# RT1064_Device.net
KiCad netlist of a schematic drawn in Altium Designer
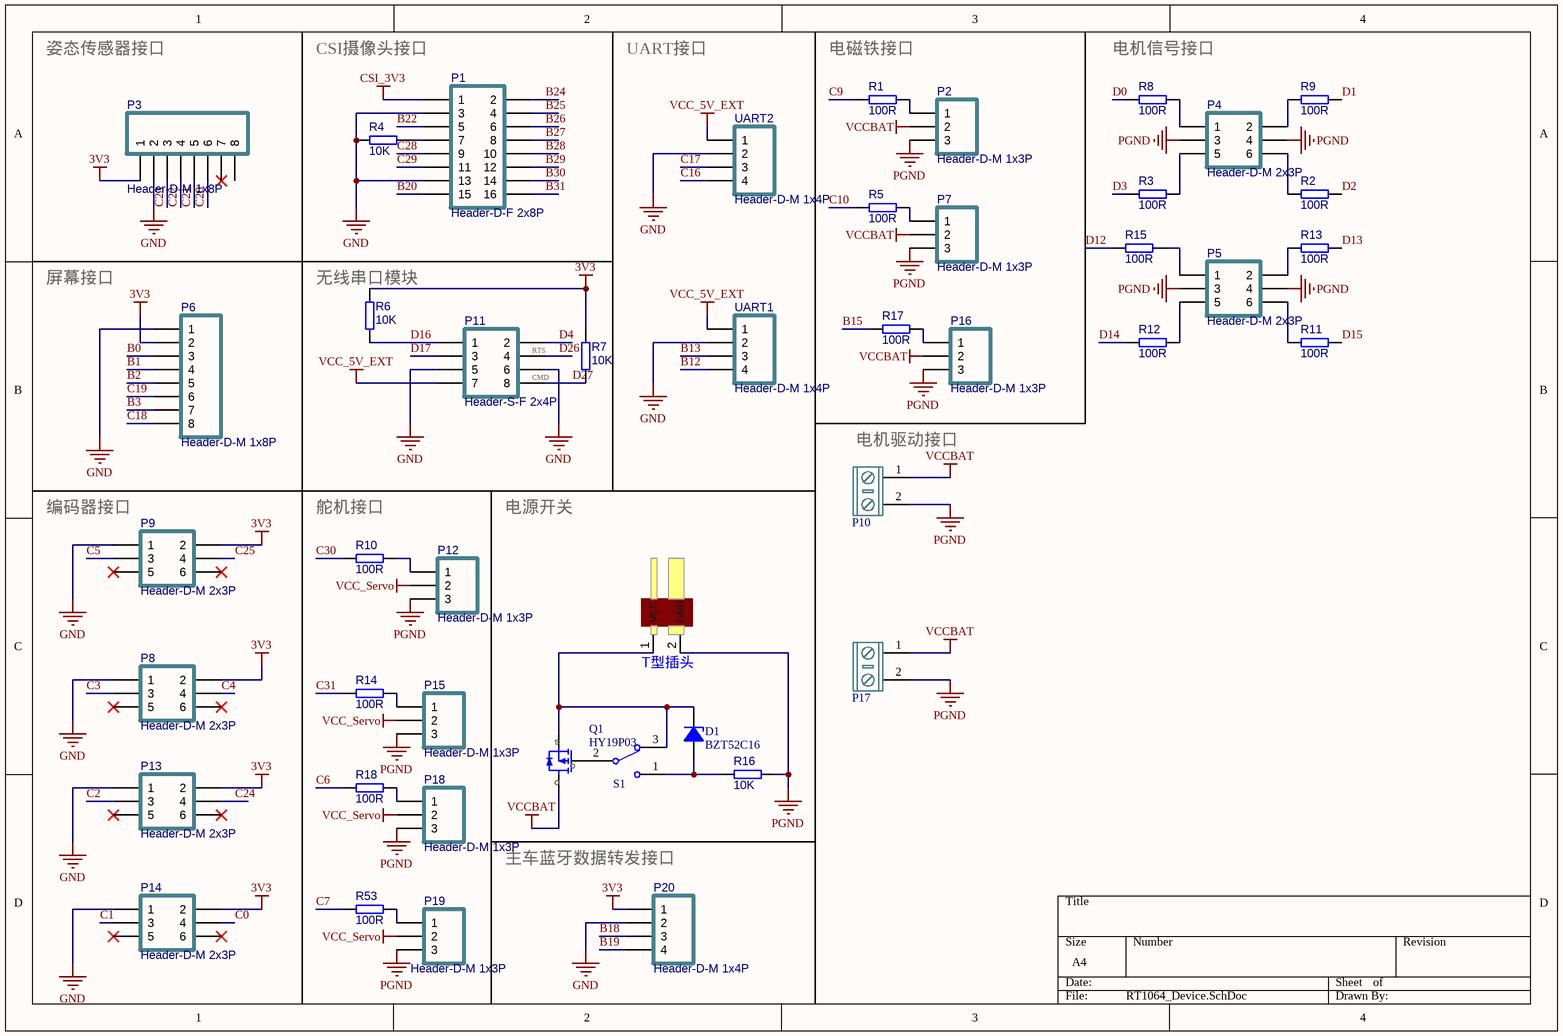
[diagram p0: RT1064_Device.SchDoc]

(export (version "E")
  (design (tool "Eeschema 10.0.6"))
  (components
    (comp (ref "D1")
      (value "BZT52C16")
      (footprint "SOD-123-L")
      (description "稳压二极管 齐纳二极管  Zener Diode")
      (fields (field (name "PUBLISHER") "Altium Limited"))
      (libsource (lib "RT1064_V1主板器件封装集成库") (part "Diode Zen"))
    )
    (comp (ref "DCIN1")
      (value "T型插头")
      (footprint "CONN-TH_AM-1015B-F")
      (libsource (lib "RT1064_V1主板器件封装集成库") (part "T_Header"))
    )
    (comp (ref "P1")
      (value "Header-D-F 2x8P")
      (footprint "Cam_HDR2X8-F-SMT")
      (description "2x8pin, 直插, 双排座")
      (libsource (lib "RT1064 主板 V3.0 器件封装集成库") (part "Header-D-F 2x8P"))
    )
    (comp (ref "P2")
      (value "Header-D-M 1x3P")
      (footprint "HDR1X3-M")
      (description "1x3pin, 直插, 排针")
      (libsource (lib "RT1064_V1主板器件封装集成库") (part "Header-D-M 1x3P"))
    )
    (comp (ref "P3")
      (value "Header-D-M 1x8P")
      (footprint "Fe-HDR1X8/2.54-S")
      (description "1x8pin, 直插, 排针")
      (libsource (lib "RT1064_V1主板器件封装集成库") (part "Header-D-M 1x8P"))
    )
    (comp (ref "P4")
      (value "Header-D-M 2x3P")
      (footprint "HDR2.54-M-LS-2x3P")
      (description "2x3pin, 贴片, 双排针")
      (libsource (lib "RT1064_V1主板器件封装集成库") (part "Header-S-M 2x3P"))
    )
    (comp (ref "P5")
      (value "Header-D-M 2x3P")
      (footprint "HDR2.54-M-LS-2x3P")
      (description "2x3pin, 贴片, 双排针")
      (libsource (lib "RT1064_V1主板器件封装集成库") (part "Header-S-M 2x3P"))
    )
    (comp (ref "P6")
      (value "Header-D-M 1x8P")
      (footprint "Fe-HDR1X8/2.54-S")
      (description "1x8pin, 直插, 排针")
      (libsource (lib "") (part "Header-D-M 1x8P_1"))
    )
    (comp (ref "P7")
      (value "Header-D-M 1x3P")
      (footprint "HDR1X3-M")
      (description "1x3pin, 直插, 排针")
      (libsource (lib "RT1064_V1主板器件封装集成库") (part "Header-D-M 1x3P"))
    )
    (comp (ref "P8")
      (value "Header-D-M 2x3P")
      (footprint "DC3-6P-2.54mm")
      (description "2x3pin, 贴片, 双排针")
      (libsource (lib "RT1064_V1主板器件封装集成库") (part "Header-S-M 2x3P"))
    )
    (comp (ref "P9")
      (value "Header-D-M 2x3P")
      (footprint "DC3-6P-2.54mm")
      (description "2x3pin, 贴片, 双排针")
      (libsource (lib "RT1064_V1主板器件封装集成库") (part "Header-S-M 2x3P"))
    )
    (comp (ref "P10")
      (value "KF/WJ/DG 30x connecter")
      (footprint "KF/WJ/DG 301-2p-5.0mm")
      (description "接线端子 2Pin")
      (libsource (lib "RT1064_V1主板器件封装集成库") (part "KF/WJ/DG 30x"))
    )
    (comp (ref "P11")
      (value "Header-S-F 2x4P")
      (footprint "HDR2X4-F-SMT")
      (description "2x4pin, 贴片, 双排座")
      (libsource (lib "RT1064_V1主板器件封装集成库") (part "Header-S-F 2x4P"))
    )
    (comp (ref "P12")
      (value "Header-D-M 1x3P")
      (footprint "Fe-HDR1X3/2.54-S")
      (description "1x3pin, 直插, 排针")
      (libsource (lib "RT1064_V1主板器件封装集成库") (part "Header-D-M 1x3P"))
    )
    (comp (ref "P13")
      (value "Header-D-M 2x3P")
      (footprint "DC3-6P-2.54mm")
      (description "2x3pin, 贴片, 双排针")
      (libsource (lib "RT1064_V1主板器件封装集成库") (part "Header-S-M 2x3P"))
    )
    (comp (ref "P14")
      (value "Header-D-M 2x3P")
      (footprint "DC3-6P-2.54mm")
      (description "2x3pin, 贴片, 双排针")
      (libsource (lib "RT1064_V1主板器件封装集成库") (part "Header-S-M 2x3P"))
    )
    (comp (ref "P15")
      (value "Header-D-M 1x3P")
      (footprint "Fe-HDR1X3/2.54-S")
      (description "1x3pin, 直插, 排针")
      (libsource (lib "RT1064_V1主板器件封装集成库") (part "Header-D-M 1x3P"))
    )
    (comp (ref "P16")
      (value "Header-D-M 1x3P")
      (footprint "HDR1X3-M")
      (description "1x3pin, 直插, 排针")
      (libsource (lib "RT1064_V1主板器件封装集成库") (part "Header-D-M 1x3P"))
    )
    (comp (ref "P17")
      (value "KF/WJ/DG 30x connecter")
      (footprint "KF/WJ/DG 301-2p-5.0mm")
      (description "接线端子 2Pin")
      (libsource (lib "RT1064_V1主板器件封装集成库") (part "KF/WJ/DG 30x"))
    )
    (comp (ref "P18")
      (value "Header-D-M 1x3P")
      (footprint "Fe-HDR1X3/2.54-S")
      (description "1x3pin, 直插, 排针")
      (libsource (lib "RT1064_V1主板器件封装集成库") (part "Header-D-M 1x3P"))
    )
    (comp (ref "P19")
      (value "Header-D-M 1x3P")
      (footprint "Fe-HDR1X3/2.54-S")
      (description "1x3pin, 直插, 排针")
      (libsource (lib "RT1064_V1主板器件封装集成库") (part "Header-D-M 1x3P"))
    )
    (comp (ref "P20")
      (value "Header-D-M 1x4P")
      (footprint "HDR1X4-M")
      (description "1x4pin, 直插, 排针")
      (libsource (lib "RT1064_V1主板器件封装集成库") (part "Header-D-M 1x4P"))
    )
    (comp (ref "Q1")
      (value "HY19P03")
      (footprint "TO-252AA")
      (description "HY19P03 P-Channel MOSFET")
      (libsource (lib "RT1064_V1主板器件封装集成库") (part "HY19P03"))
    )
    (comp (ref "R1")
      (value "100R")
      (footprint "RESC1608[0603]S-L")
      (description "贴片电阻")
      (fields (field (name "POWER") "1/8W") (field (name "TOLERANCE") "±1%"))
      (libsource (lib "RT1064_V1主板器件封装集成库") (part "Res-Chip"))
    )
    (comp (ref "R2")
      (value "100R")
      (footprint "RESC1608[0603]S-L")
      (description "贴片电阻")
      (fields (field (name "POWER") "1/8W") (field (name "TOLERANCE") "±1%"))
      (libsource (lib "RT1064_V1主板器件封装集成库") (part "Res-Chip"))
    )
    (comp (ref "R3")
      (value "100R")
      (footprint "RESC1608[0603]S-L")
      (description "贴片电阻")
      (fields (field (name "POWER") "1/8W") (field (name "TOLERANCE") "±1%"))
      (libsource (lib "RT1064_V1主板器件封装集成库") (part "Res-Chip"))
    )
    (comp (ref "R4")
      (value "10K")
      (footprint "RESC1608[0603]S-L")
      (description "贴片电阻")
      (fields (field (name "POWER") "1/8W") (field (name "TOLERANCE") "±1%"))
      (libsource (lib "RT1064_V1主板器件封装集成库") (part "Res-Chip"))
    )
    (comp (ref "R5")
      (value "100R")
      (footprint "RESC1608[0603]S-L")
      (description "贴片电阻")
      (fields (field (name "POWER") "1/8W") (field (name "TOLERANCE") "±1%"))
      (libsource (lib "RT1064_V1主板器件封装集成库") (part "Res-Chip"))
    )
    (comp (ref "R6")
      (value "10K")
      (footprint "RESC1608[0603]S-L")
      (description "贴片电阻")
      (fields (field (name "POWER") "1/8W") (field (name "TOLERANCE") "±1%"))
      (libsource (lib "RT1064_V1主板器件封装集成库") (part "Res-Chip"))
    )
    (comp (ref "R7")
      (value "10K")
      (footprint "RESC1608[0603]S-L")
      (description "贴片电阻")
      (fields (field (name "POWER") "1/8W") (field (name "TOLERANCE") "±1%"))
      (libsource (lib "RT1064_V1主板器件封装集成库") (part "Res-Chip"))
    )
    (comp (ref "R8")
      (value "100R")
      (footprint "RESC1608[0603]S-L")
      (description "贴片电阻")
      (fields (field (name "POWER") "1/8W") (field (name "TOLERANCE") "±1%"))
      (libsource (lib "RT1064_V1主板器件封装集成库") (part "Res-Chip"))
    )
    (comp (ref "R9")
      (value "100R")
      (footprint "RESC1608[0603]S-L")
      (description "贴片电阻")
      (fields (field (name "POWER") "1/8W") (field (name "TOLERANCE") "±1%"))
      (libsource (lib "RT1064_V1主板器件封装集成库") (part "Res-Chip"))
    )
    (comp (ref "R10")
      (value "100R")
      (footprint "RESC1608[0603]S-L")
      (description "贴片电阻")
      (fields (field (name "POWER") "1/8W") (field (name "TOLERANCE") "±1%"))
      (libsource (lib "RT1064_V1主板器件封装集成库") (part "Res-Chip"))
    )
    (comp (ref "R11")
      (value "100R")
      (footprint "RESC1608[0603]S-L")
      (description "贴片电阻")
      (fields (field (name "POWER") "1/8W") (field (name "TOLERANCE") "±1%"))
      (libsource (lib "RT1064_V1主板器件封装集成库") (part "Res-Chip"))
    )
    (comp (ref "R12")
      (value "100R")
      (footprint "RESC1608[0603]S-L")
      (description "贴片电阻")
      (fields (field (name "POWER") "1/8W") (field (name "TOLERANCE") "±1%"))
      (libsource (lib "RT1064_V1主板器件封装集成库") (part "Res-Chip"))
    )
    (comp (ref "R13")
      (value "100R")
      (footprint "RESC1608[0603]S-L")
      (description "贴片电阻")
      (fields (field (name "POWER") "1/8W") (field (name "TOLERANCE") "±1%"))
      (libsource (lib "RT1064_V1主板器件封装集成库") (part "Res-Chip"))
    )
    (comp (ref "R14")
      (value "100R")
      (footprint "RESC1608[0603]S-L")
      (description "贴片电阻")
      (fields (field (name "POWER") "1/8W") (field (name "TOLERANCE") "±1%"))
      (libsource (lib "RT1064_V1主板器件封装集成库") (part "Res-Chip"))
    )
    (comp (ref "R15")
      (value "100R")
      (footprint "RESC1608[0603]S-L")
      (description "贴片电阻")
      (fields (field (name "POWER") "1/8W") (field (name "TOLERANCE") "±1%"))
      (libsource (lib "RT1064_V1主板器件封装集成库") (part "Res-Chip"))
    )
    (comp (ref "R16")
      (value "10K")
      (footprint "RESC1608[0603]S-L")
      (description "贴片电阻")
      (fields (field (name "POWER") "1/8W") (field (name "TOLERANCE") "±1%"))
      (libsource (lib "RT1064_V1主板器件封装集成库") (part "Res-Chip"))
    )
    (comp (ref "R17")
      (value "100R")
      (footprint "RESC1608[0603]S-L")
      (description "贴片电阻")
      (fields (field (name "POWER") "1/8W") (field (name "TOLERANCE") "±1%"))
      (libsource (lib "RT1064_V1主板器件封装集成库") (part "Res-Chip"))
    )
    (comp (ref "R18")
      (value "100R")
      (footprint "RESC1608[0603]S-L")
      (description "贴片电阻")
      (fields (field (name "POWER") "1/8W") (field (name "TOLERANCE") "±1%"))
      (libsource (lib "RT1064_V1主板器件封装集成库") (part "Res-Chip"))
    )
    (comp (ref "R53")
      (value "100R")
      (footprint "RESC1608[0603]S-L")
      (description "贴片电阻")
      (fields (field (name "POWER") "1/8W") (field (name "TOLERANCE") "±1%"))
      (libsource (lib "RT1064_V1主板器件封装集成库") (part "Res-Chip"))
    )
    (comp (ref "S1")
      (value "SW-SPDT")
      (footprint "SS-12F23")
      (description "单刀双掷开关 3脚船型、钮子、拨动开关 SPDT Subminiature Toggle Switch")
      (fields (field (name "PUBLISHER") "Altium Limited"))
      (libsource (lib "RT1064_V1主板器件封装集成库") (part "SW-SPDT"))
    )
    (comp (ref "UART1")
      (value "Header-D-M 1x4P")
      (footprint "XH2.54-WI-4P")
      (description "1x4pin, 直插, 排针")
      (libsource (lib "RT1064_V1主板器件封装集成库") (part "Header-D-M 1x4P"))
    )
    (comp (ref "UART2")
      (value "Header-D-M 1x4P")
      (footprint "XH2.54-WI-4P")
      (description "1x4pin, 直插, 排针")
      (libsource (lib "RT1064_V1主板器件封装集成库") (part "Header-D-M 1x4P"))
    )
  )
  (nets
    (net (code "1") (name "/B0") (class "Default")
      (node (ref "P6") (pin "3") (pinfunction "3_3") (pintype "passive"))
    )
    (net (code "2") (name "/B1") (class "Default")
      (node (ref "P6") (pin "4") (pinfunction "4_4") (pintype "passive"))
    )
    (net (code "3") (name "/B2") (class "Default")
      (node (ref "P6") (pin "5") (pinfunction "5_5") (pintype "passive"))
    )
    (net (code "4") (name "/B3") (class "Default")
      (node (ref "P6") (pin "7") (pinfunction "7_7") (pintype "passive"))
    )
    (net (code "5") (name "/B12") (class "Default")
      (node (ref "UART1") (pin "4") (pinfunction "4_4") (pintype "passive"))
    )
    (net (code "6") (name "/B13") (class "Default")
      (node (ref "UART1") (pin "3") (pinfunction "3_3") (pintype "passive"))
    )
    (net (code "7") (name "/B15") (class "Default")
      (node (ref "R17") (pin "2") (pinfunction "2_2") (pintype "passive"))
    )
    (net (code "8") (name "/B18") (class "Default")
      (node (ref "P20") (pin "3") (pinfunction "3_3") (pintype "passive"))
    )
    (net (code "9") (name "/B19") (class "Default")
      (node (ref "P20") (pin "4") (pinfunction "4_4") (pintype "passive"))
    )
    (net (code "10") (name "/B20") (class "Default")
      (node (ref "P1") (pin "15") (pinfunction "15_15") (pintype "passive"))
    )
    (net (code "11") (name "/B22") (class "Default")
      (node (ref "P1") (pin "5") (pinfunction "5_5") (pintype "passive"))
    )
    (net (code "12") (name "/B24") (class "Default")
      (node (ref "P1") (pin "2") (pinfunction "2_2") (pintype "passive"))
    )
    (net (code "13") (name "/B25") (class "Default")
      (node (ref "P1") (pin "4") (pinfunction "4_4") (pintype "passive"))
    )
    (net (code "14") (name "/B26") (class "Default")
      (node (ref "P1") (pin "6") (pinfunction "6_6") (pintype "passive"))
    )
    (net (code "15") (name "/B27") (class "Default")
      (node (ref "P1") (pin "8") (pinfunction "8_8") (pintype "passive"))
    )
    (net (code "16") (name "/B28") (class "Default")
      (node (ref "P1") (pin "10") (pinfunction "10_10") (pintype "passive"))
    )
    (net (code "17") (name "/B29") (class "Default")
      (node (ref "P1") (pin "12") (pinfunction "12_12") (pintype "passive"))
    )
    (net (code "18") (name "/B30") (class "Default")
      (node (ref "P1") (pin "14") (pinfunction "14_14") (pintype "passive"))
    )
    (net (code "19") (name "/B31") (class "Default")
      (node (ref "P1") (pin "16") (pinfunction "16_16") (pintype "passive"))
    )
    (net (code "20") (name "/C0") (class "Default")
      (node (ref "P14") (pin "4") (pinfunction "4_4") (pintype "passive"))
    )
    (net (code "21") (name "/C1") (class "Default")
      (node (ref "P14") (pin "3") (pinfunction "3_3") (pintype "passive"))
    )
    (net (code "22") (name "/C2") (class "Default")
      (node (ref "P13") (pin "3") (pinfunction "3_3") (pintype "passive"))
    )
    (net (code "23") (name "/C3") (class "Default")
      (node (ref "P8") (pin "3") (pinfunction "3_3") (pintype "passive"))
    )
    (net (code "24") (name "/C4") (class "Default")
      (node (ref "P8") (pin "4") (pinfunction "4_4") (pintype "passive"))
    )
    (net (code "25") (name "/C5") (class "Default")
      (node (ref "P9") (pin "3") (pinfunction "3_3") (pintype "passive"))
    )
    (net (code "26") (name "/C6") (class "Default")
      (node (ref "R18") (pin "2") (pinfunction "2_2") (pintype "passive"))
    )
    (net (code "27") (name "/C7") (class "Default")
      (node (ref "R53") (pin "2") (pinfunction "2_2") (pintype "passive"))
    )
    (net (code "28") (name "/C9") (class "Default")
      (node (ref "R1") (pin "2") (pinfunction "2_2") (pintype "passive"))
    )
    (net (code "29") (name "/C10") (class "Default")
      (node (ref "R5") (pin "2") (pinfunction "2_2") (pintype "passive"))
    )
    (net (code "30") (name "/C16") (class "Default")
      (node (ref "UART2") (pin "4") (pinfunction "4_4") (pintype "passive"))
    )
    (net (code "31") (name "/C17") (class "Default")
      (node (ref "UART2") (pin "3") (pinfunction "3_3") (pintype "passive"))
    )
    (net (code "32") (name "/C18") (class "Default")
      (node (ref "P6") (pin "8") (pinfunction "8_8") (pintype "passive"))
    )
    (net (code "33") (name "/C19") (class "Default")
      (node (ref "P6") (pin "6") (pinfunction "6_6") (pintype "passive"))
    )
    (net (code "34") (name "/C20") (class "Default")
      (node (ref "P3") (pin "6") (pinfunction "6_6") (pintype "passive"))
    )
    (net (code "35") (name "/C21") (class "Default")
      (node (ref "P3") (pin "5") (pinfunction "5_5") (pintype "passive"))
    )
    (net (code "36") (name "/C22") (class "Default")
      (node (ref "P3") (pin "4") (pinfunction "4_4") (pintype "passive"))
    )
    (net (code "37") (name "/C23") (class "Default")
      (node (ref "P3") (pin "3") (pinfunction "3_3") (pintype "passive"))
    )
    (net (code "38") (name "/C24") (class "Default")
      (node (ref "P13") (pin "4") (pinfunction "4_4") (pintype "passive"))
    )
    (net (code "39") (name "/C25") (class "Default")
      (node (ref "P9") (pin "4") (pinfunction "4_4") (pintype "passive"))
    )
    (net (code "40") (name "/C28") (class "Default")
      (node (ref "P1") (pin "9") (pinfunction "9_9") (pintype "passive"))
    )
    (net (code "41") (name "/C29") (class "Default")
      (node (ref "P1") (pin "11") (pinfunction "11_11") (pintype "passive"))
    )
    (net (code "42") (name "/C30") (class "Default")
      (node (ref "R10") (pin "2") (pinfunction "2_2") (pintype "passive"))
    )
    (net (code "43") (name "/C31") (class "Default")
      (node (ref "R14") (pin "2") (pinfunction "2_2") (pintype "passive"))
    )
    (net (code "44") (name "/D0") (class "Default")
      (node (ref "R8") (pin "1") (pinfunction "1_1") (pintype "passive"))
    )
    (net (code "45") (name "/D1") (class "Default")
      (node (ref "R9") (pin "1") (pinfunction "1_1") (pintype "passive"))
    )
    (net (code "46") (name "/D2") (class "Default")
      (node (ref "R2") (pin "1") (pinfunction "1_1") (pintype "passive"))
    )
    (net (code "47") (name "/D3") (class "Default")
      (node (ref "R3") (pin "1") (pinfunction "1_1") (pintype "passive"))
    )
    (net (code "48") (name "/D4") (class "Default")
      (node (ref "P11") (pin "2") (pinfunction "2_2") (pintype "passive"))
    )
    (net (code "49") (name "/D12") (class "Default")
      (node (ref "R15") (pin "1") (pinfunction "1_1") (pintype "passive"))
    )
    (net (code "50") (name "/D13") (class "Default")
      (node (ref "R13") (pin "1") (pinfunction "1_1") (pintype "passive"))
    )
    (net (code "51") (name "/D14") (class "Default")
      (node (ref "R12") (pin "1") (pinfunction "1_1") (pintype "passive"))
    )
    (net (code "52") (name "/D15") (class "Default")
      (node (ref "R11") (pin "1") (pinfunction "1_1") (pintype "passive"))
    )
    (net (code "53") (name "/D16") (class "Default")
      (node (ref "P11") (pin "1") (pinfunction "1_1") (pintype "passive"))
      (node (ref "R6") (pin "1") (pinfunction "1_1") (pintype "passive"))
    )
    (net (code "54") (name "/D17") (class "Default")
      (node (ref "P11") (pin "3") (pinfunction "3_3") (pintype "passive"))
    )
    (net (code "55") (name "/D26") (class "Default")
      (node (ref "P11") (pin "4") (pinfunction "4_4") (pintype "passive"))
    )
    (net (code "56") (name "/D27") (class "Default")
      (node (ref "P11") (pin "8") (pinfunction "8_8") (pintype "passive"))
      (node (ref "R7") (pin "1") (pinfunction "1_1") (pintype "passive"))
    )
    (net (code "57") (name "3V3") (class "Default")
      (node (ref "P13") (pin "2") (pinfunction "2_2") (pintype "passive"))
      (node (ref "P14") (pin "2") (pinfunction "2_2") (pintype "passive"))
      (node (ref "P20") (pin "1") (pinfunction "1_1") (pintype "passive"))
      (node (ref "P3") (pin "1") (pinfunction "1_1") (pintype "passive"))
      (node (ref "P6") (pin "2") (pinfunction "2_2") (pintype "passive"))
      (node (ref "P8") (pin "2") (pinfunction "2_2") (pintype "passive"))
      (node (ref "P9") (pin "2") (pinfunction "2_2") (pintype "passive"))
      (node (ref "R6") (pin "2") (pinfunction "2_2") (pintype "passive"))
      (node (ref "R7") (pin "2") (pinfunction "2_2") (pintype "passive"))
    )
    (net (code "58") (name "CSI_3V3") (class "Default")
      (node (ref "P1") (pin "1") (pinfunction "1_1") (pintype "passive"))
    )
    (net (code "59") (name "GND") (class "Default")
      (node (ref "P1") (pin "13") (pinfunction "13_13") (pintype "passive"))
      (node (ref "P1") (pin "3") (pinfunction "3_3") (pintype "passive"))
      (node (ref "P11") (pin "5") (pinfunction "5_5") (pintype "passive"))
      (node (ref "P11") (pin "6") (pinfunction "6_6") (pintype "passive"))
      (node (ref "P13") (pin "1") (pinfunction "1_1") (pintype "passive"))
      (node (ref "P14") (pin "1") (pinfunction "1_1") (pintype "passive"))
      (node (ref "P20") (pin "2") (pinfunction "2_2") (pintype "passive"))
      (node (ref "P3") (pin "2") (pinfunction "2_2") (pintype "passive"))
      (node (ref "P6") (pin "1") (pinfunction "1_1") (pintype "passive"))
      (node (ref "P8") (pin "1") (pinfunction "1_1") (pintype "passive"))
      (node (ref "P9") (pin "1") (pinfunction "1_1") (pintype "passive"))
      (node (ref "R4") (pin "2") (pinfunction "2_2") (pintype "passive"))
      (node (ref "UART1") (pin "2") (pinfunction "2_2") (pintype "passive"))
      (node (ref "UART2") (pin "2") (pinfunction "2_2") (pintype "passive"))
    )
    (net (code "60") (name "Net-(D1-PadA)") (class "Default")
      (node (ref "D1") (pin "A") (pinfunction "A_A") (pintype "passive"))
      (node (ref "R16") (pin "2") (pinfunction "2_2") (pintype "passive"))
      (node (ref "S1") (pin "1") (pintype "passive"))
    )
    (net (code "61") (name "Net-(DCIN1-VCC)") (class "Default")
      (node (ref "D1") (pin "K") (pinfunction "K_K") (pintype "passive"))
      (node (ref "DCIN1") (pin "1") (pinfunction "VCC_1") (pintype "passive"))
      (node (ref "Q1") (pin "3") (pinfunction "S_3") (pintype "passive"))
      (node (ref "S1") (pin "3") (pintype "passive"))
    )
    (net (code "62") (name "Net-(P1-Pad7)") (class "Default")
      (node (ref "P1") (pin "7") (pinfunction "7_7") (pintype "passive"))
      (node (ref "R4") (pin "1") (pinfunction "1_1") (pintype "passive"))
    )
    (net (code "63") (name "Net-(P2-Pad1)") (class "Default")
      (node (ref "P2") (pin "1") (pinfunction "1_1") (pintype "passive"))
      (node (ref "R1") (pin "1") (pinfunction "1_1") (pintype "passive"))
    )
    (net (code "64") (name "Net-(P4-Pad1)") (class "Default")
      (node (ref "P4") (pin "1") (pinfunction "1_1") (pintype "passive"))
      (node (ref "R8") (pin "2") (pinfunction "2_2") (pintype "passive"))
    )
    (net (code "65") (name "Net-(P4-Pad2)") (class "Default")
      (node (ref "P4") (pin "2") (pinfunction "2_2") (pintype "passive"))
      (node (ref "R9") (pin "2") (pinfunction "2_2") (pintype "passive"))
    )
    (net (code "66") (name "Net-(P4-Pad5)") (class "Default")
      (node (ref "P4") (pin "5") (pinfunction "5_5") (pintype "passive"))
      (node (ref "R3") (pin "2") (pinfunction "2_2") (pintype "passive"))
    )
    (net (code "67") (name "Net-(P4-Pad6)") (class "Default")
      (node (ref "P4") (pin "6") (pinfunction "6_6") (pintype "passive"))
      (node (ref "R2") (pin "2") (pinfunction "2_2") (pintype "passive"))
    )
    (net (code "68") (name "Net-(P5-Pad1)") (class "Default")
      (node (ref "P5") (pin "1") (pinfunction "1_1") (pintype "passive"))
      (node (ref "R15") (pin "2") (pinfunction "2_2") (pintype "passive"))
    )
    (net (code "69") (name "Net-(P5-Pad2)") (class "Default")
      (node (ref "P5") (pin "2") (pinfunction "2_2") (pintype "passive"))
      (node (ref "R13") (pin "2") (pinfunction "2_2") (pintype "passive"))
    )
    (net (code "70") (name "Net-(P5-Pad5)") (class "Default")
      (node (ref "P5") (pin "5") (pinfunction "5_5") (pintype "passive"))
      (node (ref "R12") (pin "2") (pinfunction "2_2") (pintype "passive"))
    )
    (net (code "71") (name "Net-(P5-Pad6)") (class "Default")
      (node (ref "P5") (pin "6") (pinfunction "6_6") (pintype "passive"))
      (node (ref "R11") (pin "2") (pinfunction "2_2") (pintype "passive"))
    )
    (net (code "72") (name "Net-(P7-Pad1)") (class "Default")
      (node (ref "P7") (pin "1") (pinfunction "1_1") (pintype "passive"))
      (node (ref "R5") (pin "1") (pinfunction "1_1") (pintype "passive"))
    )
    (net (code "73") (name "Net-(P12-Pad1)") (class "Default")
      (node (ref "P12") (pin "1") (pinfunction "1_1") (pintype "passive"))
      (node (ref "R10") (pin "1") (pinfunction "1_1") (pintype "passive"))
    )
    (net (code "74") (name "Net-(P15-Pad1)") (class "Default")
      (node (ref "P15") (pin "1") (pinfunction "1_1") (pintype "passive"))
      (node (ref "R14") (pin "1") (pinfunction "1_1") (pintype "passive"))
    )
    (net (code "75") (name "Net-(P16-Pad1)") (class "Default")
      (node (ref "P16") (pin "1") (pinfunction "1_1") (pintype "passive"))
      (node (ref "R17") (pin "1") (pinfunction "1_1") (pintype "passive"))
    )
    (net (code "76") (name "Net-(P18-Pad1)") (class "Default")
      (node (ref "P18") (pin "1") (pinfunction "1_1") (pintype "passive"))
      (node (ref "R18") (pin "1") (pinfunction "1_1") (pintype "passive"))
    )
    (net (code "77") (name "Net-(P19-Pad1)") (class "Default")
      (node (ref "P19") (pin "1") (pinfunction "1_1") (pintype "passive"))
      (node (ref "R53") (pin "1") (pinfunction "1_1") (pintype "passive"))
    )
    (net (code "78") (name "Net-(Q1-G)") (class "Default")
      (node (ref "Q1") (pin "2") (pinfunction "G_2") (pintype "passive"))
      (node (ref "S1") (pin "2") (pintype "passive"))
    )
    (net (code "79") (name "PGND") (class "Default")
      (node (ref "DCIN1") (pin "2") (pinfunction "GND_2") (pintype "passive"))
      (node (ref "P10") (pin "2") (pinfunction "2_2") (pintype "passive"))
      (node (ref "P12") (pin "3") (pinfunction "3_3") (pintype "passive"))
      (node (ref "P15") (pin "3") (pinfunction "3_3") (pintype "passive"))
      (node (ref "P16") (pin "3") (pinfunction "3_3") (pintype "passive"))
      (node (ref "P17") (pin "2") (pinfunction "2_2") (pintype "passive"))
      (node (ref "P18") (pin "3") (pinfunction "3_3") (pintype "passive"))
      (node (ref "P19") (pin "3") (pinfunction "3_3") (pintype "passive"))
      (node (ref "P2") (pin "3") (pinfunction "3_3") (pintype "passive"))
      (node (ref "P4") (pin "3") (pinfunction "3_3") (pintype "passive"))
      (node (ref "P4") (pin "4") (pinfunction "4_4") (pintype "passive"))
      (node (ref "P5") (pin "3") (pinfunction "3_3") (pintype "passive"))
      (node (ref "P5") (pin "4") (pinfunction "4_4") (pintype "passive"))
      (node (ref "P7") (pin "3") (pinfunction "3_3") (pintype "passive"))
      (node (ref "R16") (pin "1") (pinfunction "1_1") (pintype "passive"))
    )
    (net (code "80") (name "VCCBAT") (class "Default")
      (node (ref "P10") (pin "1") (pinfunction "1_1") (pintype "passive"))
      (node (ref "P16") (pin "2") (pinfunction "2_2") (pintype "passive"))
      (node (ref "P17") (pin "1") (pinfunction "1_1") (pintype "passive"))
      (node (ref "P2") (pin "2") (pinfunction "2_2") (pintype "passive"))
      (node (ref "P7") (pin "2") (pinfunction "2_2") (pintype "passive"))
      (node (ref "Q1") (pin "1") (pinfunction "D_1") (pintype "passive"))
    )
    (net (code "81") (name "VCC_5V_EXT") (class "Default")
      (node (ref "P11") (pin "7") (pinfunction "7_7") (pintype "passive"))
      (node (ref "UART1") (pin "1") (pinfunction "1_1") (pintype "passive"))
      (node (ref "UART2") (pin "1") (pinfunction "1_1") (pintype "passive"))
    )
    (net (code "82") (name "VCC_Servo") (class "Default")
      (node (ref "P12") (pin "2") (pinfunction "2_2") (pintype "passive"))
      (node (ref "P15") (pin "2") (pinfunction "2_2") (pintype "passive"))
      (node (ref "P18") (pin "2") (pinfunction "2_2") (pintype "passive"))
      (node (ref "P19") (pin "2") (pinfunction "2_2") (pintype "passive"))
    )
    (net (code "83") (name "unconnected-(P3-Pad7)") (class "Default")
      (node (ref "P3") (pin "7") (pinfunction "7_7") (pintype "passive+no_connect"))
    )
    (net (code "84") (name "unconnected-(P3-Pad8)") (class "Default")
      (node (ref "P3") (pin "8") (pinfunction "8_8") (pintype "passive"))
    )
    (net (code "85") (name "unconnected-(P8-Pad5)") (class "Default")
      (node (ref "P8") (pin "5") (pinfunction "5_5") (pintype "passive+no_connect"))
    )
    (net (code "86") (name "unconnected-(P8-Pad6)") (class "Default")
      (node (ref "P8") (pin "6") (pinfunction "6_6") (pintype "passive+no_connect"))
    )
    (net (code "87") (name "unconnected-(P9-Pad5)") (class "Default")
      (node (ref "P9") (pin "5") (pinfunction "5_5") (pintype "passive+no_connect"))
    )
    (net (code "88") (name "unconnected-(P9-Pad6)") (class "Default")
      (node (ref "P9") (pin "6") (pinfunction "6_6") (pintype "passive+no_connect"))
    )
    (net (code "89") (name "unconnected-(P13-Pad5)") (class "Default")
      (node (ref "P13") (pin "5") (pinfunction "5_5") (pintype "passive+no_connect"))
    )
    (net (code "90") (name "unconnected-(P13-Pad6)") (class "Default")
      (node (ref "P13") (pin "6") (pinfunction "6_6") (pintype "passive+no_connect"))
    )
    (net (code "91") (name "unconnected-(P14-Pad5)") (class "Default")
      (node (ref "P14") (pin "5") (pinfunction "5_5") (pintype "passive+no_connect"))
    )
    (net (code "92") (name "unconnected-(P14-Pad6)") (class "Default")
      (node (ref "P14") (pin "6") (pinfunction "6_6") (pintype "passive+no_connect"))
    )
  )
)
